# Rover-3_Power_Supply.net
KiCad netlist of a schematic drawn in EAGLE
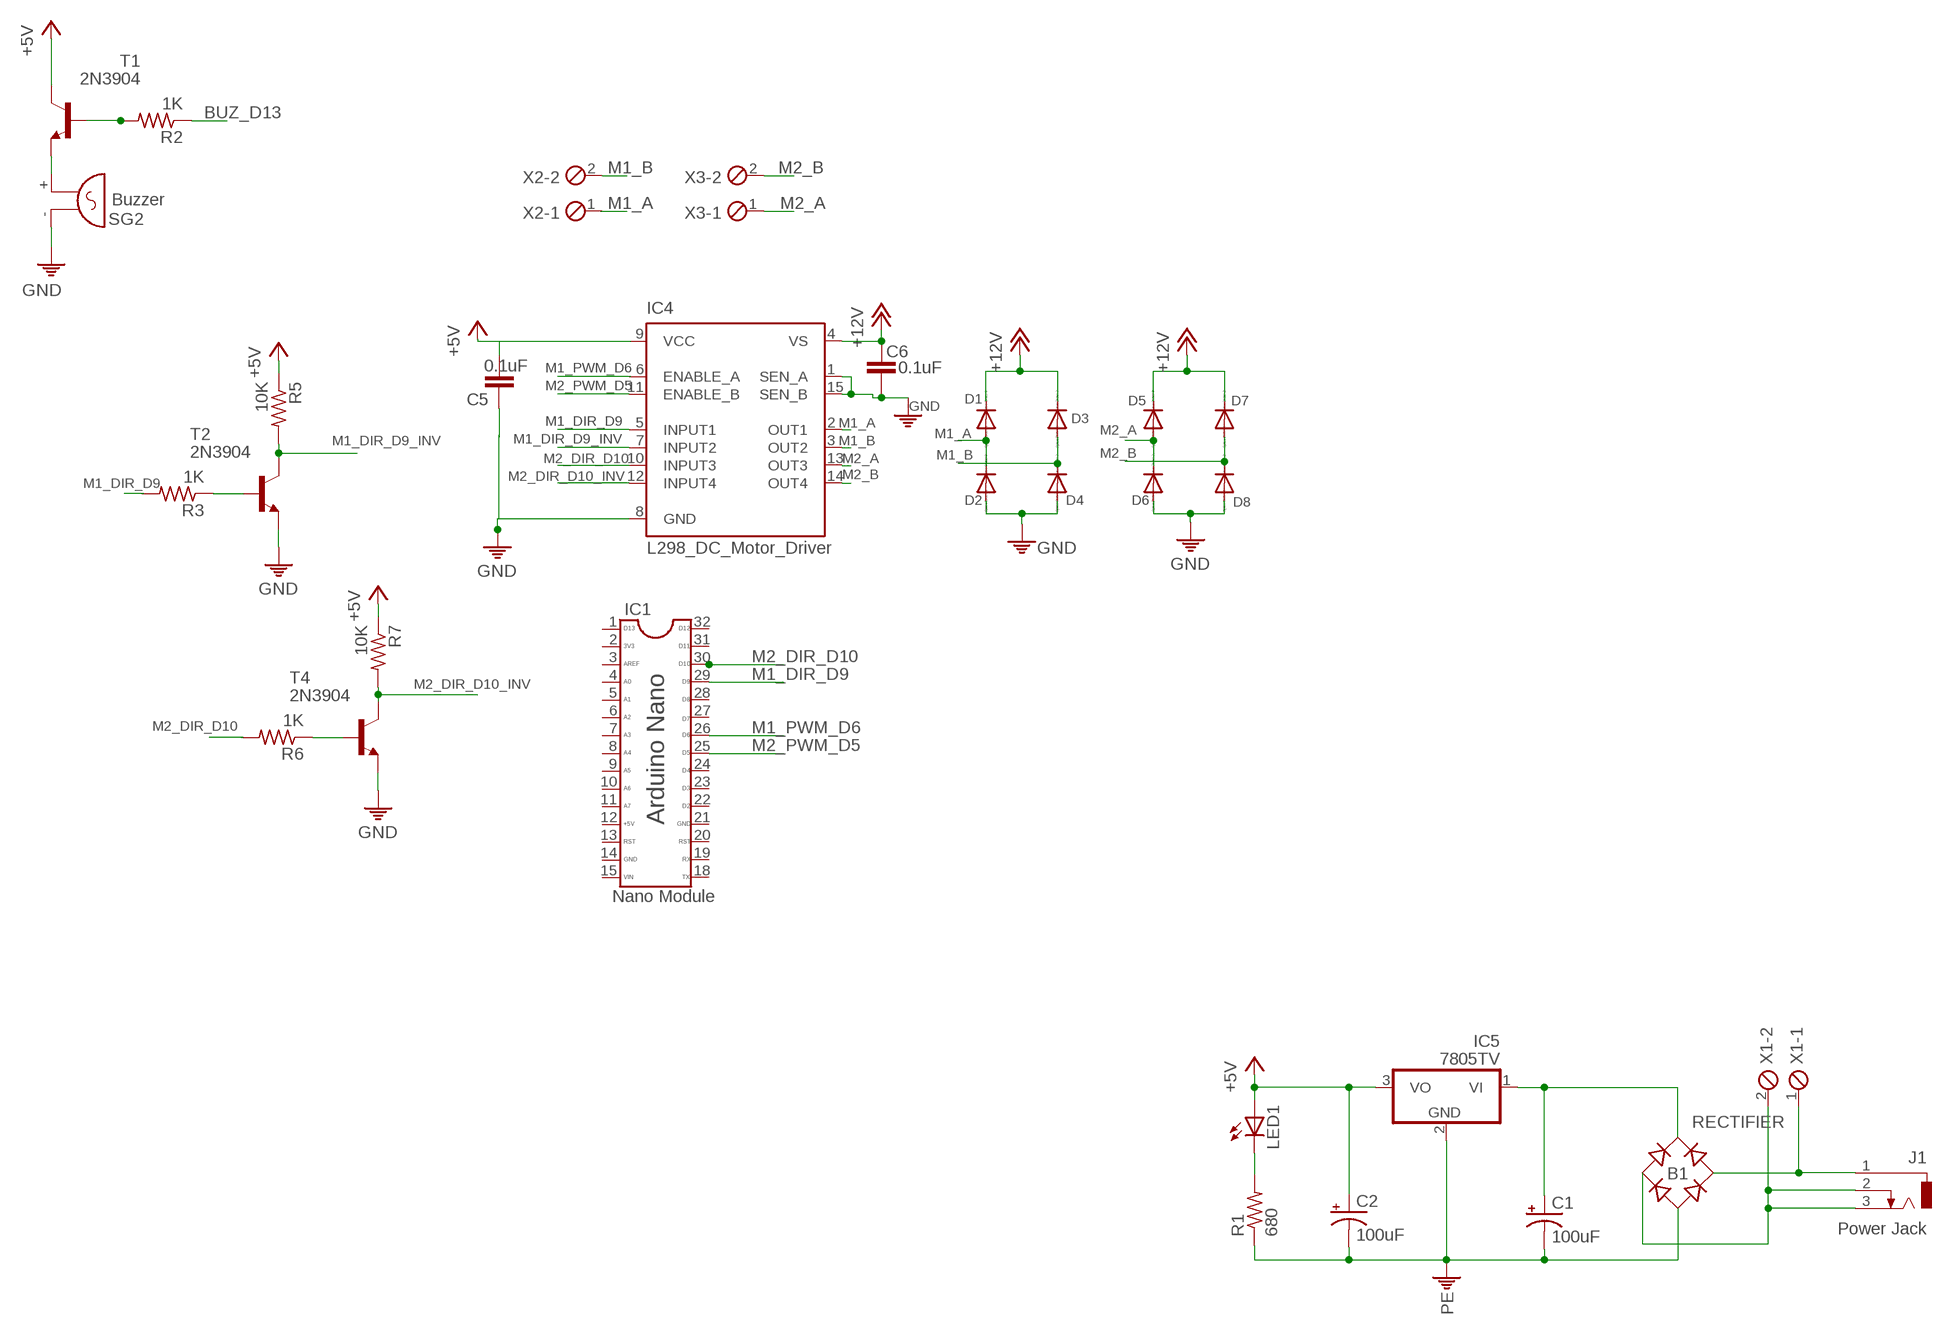
[diagram p0: schematic, sheet 1]

(export (version "E")
  (design (tool "Eeschema 10.0.6"))
  (components
    (comp (ref "B1")
      (value "RECTIFIER")
      (footprint "eagle-import:RB1A")
      (libsource (lib "eagle-import") (part "RB1A"))
    )
    (comp (ref "C1")
      (value "100uF")
      (footprint "eagle-import:E5-8,5")
      (libsource (lib "eagle-import") (part "CPOL-USE5-8.5"))
    )
    (comp (ref "C2")
      (value "100uF")
      (footprint "eagle-import:E5-8,5")
      (libsource (lib "eagle-import") (part "CPOL-USE5-8.5"))
    )
    (comp (ref "C5")
      (value "0.1uF")
      (footprint "eagle-import:C025-024X044")
      (libsource (lib "eagle-import") (part "C-EU025-024X044"))
    )
    (comp (ref "C6")
      (value "0.1uF")
      (footprint "eagle-import:C025-024X044")
      (libsource (lib "eagle-import") (part "C-EU025-024X044"))
    )
    (comp (ref "D1")
      (value "DIODE-D-2.5")
      (footprint "eagle-import:D-2.5")
      (libsource (lib "eagle-import") (part "DIODE-D-2.5"))
    )
    (comp (ref "D2")
      (value "DIODE-D-2.5")
      (footprint "eagle-import:D-2.5")
      (libsource (lib "eagle-import") (part "DIODE-D-2.5"))
    )
    (comp (ref "D3")
      (value "DIODE-D-2.5")
      (footprint "eagle-import:D-2.5")
      (libsource (lib "eagle-import") (part "DIODE-D-2.5"))
    )
    (comp (ref "D4")
      (value "DIODE-D-2.5")
      (footprint "eagle-import:D-2.5")
      (libsource (lib "eagle-import") (part "DIODE-D-2.5"))
    )
    (comp (ref "D5")
      (value "DIODE-D-2.5")
      (footprint "eagle-import:D-2.5")
      (libsource (lib "eagle-import") (part "DIODE-D-2.5"))
    )
    (comp (ref "D6")
      (value "DIODE-D-2.5")
      (footprint "eagle-import:D-2.5")
      (libsource (lib "eagle-import") (part "DIODE-D-2.5"))
    )
    (comp (ref "D7")
      (value "DIODE-D-2.5")
      (footprint "eagle-import:D-2.5")
      (libsource (lib "eagle-import") (part "DIODE-D-2.5"))
    )
    (comp (ref "D8")
      (value "DIODE-D-2.5")
      (footprint "eagle-import:D-2.5")
      (libsource (lib "eagle-import") (part "DIODE-D-2.5"))
    )
    (comp (ref "IC1")
      (value "Nano Module")
      (footprint "eagle-import:DIL32")
      (libsource (lib "eagle-import") (part "DIL32"))
    )
    (comp (ref "IC4")
      (value "L298_DC_Motor_Driver")
      (footprint "eagle-import:MULTIWATT-15")
      (fields (field (name "MPN") "L298N"))
      (libsource (lib "eagle-import") (part "L298"))
    )
    (comp (ref "IC5")
      (value "7805TV")
      (footprint "eagle-import:TO220V")
      (libsource (lib "eagle-import") (part "78TV05"))
    )
    (comp (ref "J1")
      (value "Power Jack")
      (footprint "eagle-import:ROVER-PW-JACL")
      (libsource (lib "eagle-import") (part "DCJ0303"))
    )
    (comp (ref "LED1")
      (value "LED3MM")
      (footprint "eagle-import:LED3MM")
      (libsource (lib "eagle-import") (part "LED3MM"))
    )
    (comp (ref "R1")
      (value "680")
      (footprint "eagle-import:0204_5")
      (libsource (lib "eagle-import") (part "R-US_0204/5"))
    )
    (comp (ref "R2")
      (value "1K")
      (footprint "eagle-import:0204_5")
      (libsource (lib "eagle-import") (part "R-US_0204/5"))
    )
    (comp (ref "R3")
      (value "1K")
      (footprint "eagle-import:0204_5")
      (libsource (lib "eagle-import") (part "R-US_0204/5"))
    )
    (comp (ref "R5")
      (value "10K")
      (footprint "eagle-import:0204_5")
      (libsource (lib "eagle-import") (part "R-US_0204/5"))
    )
    (comp (ref "R6")
      (value "1K")
      (footprint "eagle-import:0204_5")
      (libsource (lib "eagle-import") (part "R-US_0204/5"))
    )
    (comp (ref "R7")
      (value "10K")
      (footprint "eagle-import:0204_5")
      (libsource (lib "eagle-import") (part "R-US_0204/5"))
    )
    (comp (ref "SG2")
      (value "Buzzer")
      (footprint "eagle-import:F_QMX")
      (libsource (lib "eagle-import") (part "F/QMX"))
    )
    (comp (ref "T1")
      (value "2N3904")
      (footprint "eagle-import:TO92")
      (libsource (lib "eagle-import") (part "2N3904"))
    )
    (comp (ref "T2")
      (value "2N3904")
      (footprint "eagle-import:TO92")
      (libsource (lib "eagle-import") (part "2N3904"))
    )
    (comp (ref "T4")
      (value "2N3904")
      (footprint "eagle-import:TO92")
      (libsource (lib "eagle-import") (part "2N3904"))
    )
    (comp (ref "X1")
      (value "MPT2")
      (footprint "eagle-import:2POL254")
      (libsource (lib "eagle-import") (part "MPT2"))
    )
    (comp (ref "X2")
      (value "MPT2")
      (footprint "eagle-import:2POL254")
      (libsource (lib "eagle-import") (part "MPT2"))
    )
    (comp (ref "X3")
      (value "MPT2")
      (footprint "eagle-import:2POL254")
      (libsource (lib "eagle-import") (part "MPT2"))
    )
  )
  (nets
    (net (code "1") (name "+5V") (class "Default")
      (node (ref "C2") (pin "+") (pinfunction "+_+") (pintype "passive"))
      (node (ref "C5") (pin "2") (pinfunction "2_2") (pintype "passive"))
      (node (ref "IC5") (pin "3") (pinfunction "VO_3") (pintype "passive"))
      (node (ref "LED1") (pin "A") (pinfunction "A_A") (pintype "passive"))
      (node (ref "R5") (pin "1") (pinfunction "1_1") (pintype "passive"))
      (node (ref "R7") (pin "1") (pinfunction "1_1") (pintype "passive"))
      (node (ref "T1") (pin "1") (pinfunction "C_1") (pintype "passive"))
    )
    (net (code "2") (name "+12V") (class "Default")
      (node (ref "C6") (pin "2") (pinfunction "2_2") (pintype "passive"))
      (node (ref "D1") (pin "C") (pinfunction "C_C") (pintype "passive"))
      (node (ref "D3") (pin "C") (pinfunction "C_C") (pintype "passive"))
      (node (ref "D5") (pin "C") (pinfunction "C_C") (pintype "passive"))
      (node (ref "D7") (pin "C") (pinfunction "C_C") (pintype "passive"))
      (node (ref "IC4") (pin "4") (pinfunction "VS_4") (pintype "power_in"))
    )
    (net (code "3") (name "/BUZ_D13") (class "Default")
      (node (ref "R2") (pin "1") (pinfunction "1_1") (pintype "passive"))
    )
    (net (code "4") (name "/M1_A") (class "Default")
      (node (ref "D1") (pin "A") (pinfunction "A_A") (pintype "passive"))
      (node (ref "D2") (pin "C") (pinfunction "C_C") (pintype "passive"))
      (node (ref "IC4") (pin "2") (pinfunction "OUT1_2") (pintype "output"))
    )
    (net (code "5") (name "/M1_B") (class "Default")
      (node (ref "D3") (pin "A") (pinfunction "A_A") (pintype "passive"))
      (node (ref "D4") (pin "C") (pinfunction "C_C") (pintype "passive"))
      (node (ref "IC4") (pin "3") (pinfunction "OUT2_3") (pintype "output"))
      (node (ref "X2") (pin "2") (pinfunction "1_2") (pintype "passive"))
    )
    (net (code "6") (name "/M1_DIR_D9") (class "Default")
      (node (ref "IC1") (pin "29") (pinfunction "D9/PWM_29") (pintype "passive"))
      (node (ref "IC4") (pin "5") (pinfunction "INPUT1_5") (pintype "input"))
    )
    (net (code "7") (name "/M1_DIR_D9_INV") (class "Default")
      (node (ref "IC4") (pin "7") (pinfunction "INPUT2_7") (pintype "input"))
      (node (ref "R5") (pin "2") (pinfunction "2_2") (pintype "passive"))
      (node (ref "T2") (pin "1") (pinfunction "C_1") (pintype "passive"))
    )
    (net (code "8") (name "/M1_PWM_D6") (class "Default")
      (node (ref "IC1") (pin "26") (pinfunction "D6/PWM_26") (pintype "passive"))
    )
    (net (code "9") (name "/M2_A") (class "Default")
      (node (ref "D5") (pin "A") (pinfunction "A_A") (pintype "passive"))
      (node (ref "D6") (pin "C") (pinfunction "C_C") (pintype "passive"))
      (node (ref "IC4") (pin "13") (pinfunction "OUT3_13") (pintype "output"))
      (node (ref "X3") (pin "1") (pinfunction "1_1") (pintype "passive"))
    )
    (net (code "10") (name "/M2_B") (class "Default")
      (node (ref "D7") (pin "A") (pinfunction "A_A") (pintype "passive"))
      (node (ref "D8") (pin "C") (pinfunction "C_C") (pintype "passive"))
      (node (ref "IC4") (pin "14") (pinfunction "OUT4_14") (pintype "output"))
      (node (ref "X3") (pin "2") (pinfunction "1_2") (pintype "passive"))
    )
    (net (code "11") (name "/M2_DIR_D10") (class "Default")
      (node (ref "IC1") (pin "30") (pinfunction "D10/PWM_30") (pintype "passive"))
      (node (ref "IC4") (pin "10") (pinfunction "INPUT3_10") (pintype "input"))
    )
    (net (code "12") (name "/M2_DIR_D10_INV") (class "Default")
      (node (ref "IC4") (pin "12") (pinfunction "INPUT4_12") (pintype "input"))
      (node (ref "R7") (pin "2") (pinfunction "2_2") (pintype "passive"))
      (node (ref "T4") (pin "1") (pinfunction "C_1") (pintype "passive"))
    )
    (net (code "13") (name "/M2_PWM_D5") (class "Default")
      (node (ref "IC1") (pin "25") (pinfunction "D5/PWM_25") (pintype "passive"))
      (node (ref "IC4") (pin "11") (pinfunction "ENABLE_B_11") (pintype "input"))
    )
    (net (code "14") (name "/VCC") (class "Default")
      (node (ref "IC4") (pin "9") (pinfunction "VCC_9") (pintype "power_in"))
    )
    (net (code "15") (name "GND") (class "Default")
      (node (ref "B1") (pin "-") (pinfunction "-_-") (pintype "passive"))
      (node (ref "C1") (pin "-") (pinfunction "-_-") (pintype "passive"))
      (node (ref "C2") (pin "-") (pinfunction "-_-") (pintype "passive"))
      (node (ref "C6") (pin "1") (pinfunction "1_1") (pintype "passive"))
      (node (ref "D2") (pin "A") (pinfunction "A_A") (pintype "passive"))
      (node (ref "D4") (pin "A") (pinfunction "A_A") (pintype "passive"))
      (node (ref "D6") (pin "A") (pinfunction "A_A") (pintype "passive"))
      (node (ref "D8") (pin "A") (pinfunction "A_A") (pintype "passive"))
      (node (ref "IC4") (pin "1") (pinfunction "SEN_A_1") (pintype "input"))
      (node (ref "IC4") (pin "15") (pinfunction "SEN_B_15") (pintype "input"))
      (node (ref "IC4") (pin "8") (pinfunction "GND_8") (pintype "power_in"))
      (node (ref "IC5") (pin "2") (pinfunction "GND_2") (pintype "passive"))
      (node (ref "R1") (pin "1") (pinfunction "1_1") (pintype "passive"))
      (node (ref "SG2") (pin "-") (pinfunction "1_-") (pintype "passive"))
      (node (ref "T2") (pin "3") (pinfunction "E_3") (pintype "passive"))
      (node (ref "T4") (pin "3") (pinfunction "E_3") (pintype "passive"))
    )
    (net (code "16") (name "Net-(B1-PadAC1)") (class "Default")
      (node (ref "B1") (pin "AC1") (pinfunction "AC1_AC1") (pintype "passive"))
      (node (ref "J1") (pin "1") (pinfunction "1_1") (pintype "passive"))
      (node (ref "X1") (pin "1") (pinfunction "1_1") (pintype "passive"))
    )
    (net (code "17") (name "Net-(IC5-VI)") (class "Default")
      (node (ref "B1") (pin "+") (pinfunction "+_+") (pintype "passive"))
      (node (ref "C1") (pin "+") (pinfunction "+_+") (pintype "passive"))
      (node (ref "IC5") (pin "1") (pinfunction "VI_1") (pintype "input"))
    )
    (net (code "18") (name "Net-(LED1-C)") (class "Default")
      (node (ref "LED1") (pin "K") (pinfunction "C_K") (pintype "passive"))
      (node (ref "R1") (pin "2") (pinfunction "2_2") (pintype "passive"))
    )
    (net (code "19") (name "Net-(SG2-2)") (class "Default")
      (node (ref "SG2") (pin "+") (pinfunction "2_+") (pintype "passive"))
      (node (ref "T1") (pin "3") (pinfunction "E_3") (pintype "passive"))
    )
    (net (code "20") (name "Net-(T1-B)") (class "Default")
      (node (ref "R2") (pin "2") (pinfunction "2_2") (pintype "passive"))
      (node (ref "T1") (pin "2") (pinfunction "B_2") (pintype "passive"))
    )
    (net (code "21") (name "Net-(T2-B)") (class "Default")
      (node (ref "R3") (pin "1") (pinfunction "1_1") (pintype "passive"))
      (node (ref "T2") (pin "2") (pinfunction "B_2") (pintype "passive"))
    )
    (net (code "22") (name "Net-(T4-B)") (class "Default")
      (node (ref "R6") (pin "1") (pinfunction "1_1") (pintype "passive"))
      (node (ref "T4") (pin "2") (pinfunction "B_2") (pintype "passive"))
    )
    (net (code "23") (name "Net-(X1B-1)") (class "Default")
      (node (ref "B1") (pin "AC2") (pinfunction "AC2_AC2") (pintype "passive"))
      (node (ref "J1") (pin "2") (pinfunction "2_2") (pintype "passive"))
      (node (ref "J1") (pin "3") (pinfunction "3_3") (pintype "passive"))
      (node (ref "X1") (pin "2") (pinfunction "1_2") (pintype "passive"))
    )
    (net (code "24") (name "unconnected-(C5-Pad1)") (class "Default")
      (node (ref "C5") (pin "1") (pinfunction "1_1") (pintype "passive"))
    )
    (net (code "25") (name "unconnected-(IC1-3V3-Pad2)") (class "Default")
      (node (ref "IC1") (pin "2") (pinfunction "3V3_2") (pintype "passive"))
    )
    (net (code "26") (name "unconnected-(IC1-5V-Pad12)") (class "Default")
      (node (ref "IC1") (pin "12") (pinfunction "5V_12") (pintype "passive"))
    )
    (net (code "27") (name "unconnected-(IC1-A0{slash}D14-Pad4)") (class "Default")
      (node (ref "IC1") (pin "4") (pinfunction "A0/D14_4") (pintype "passive"))
    )
    (net (code "28") (name "unconnected-(IC1-A1{slash}D15-Pad5)") (class "Default")
      (node (ref "IC1") (pin "5") (pinfunction "A1/D15_5") (pintype "passive"))
    )
    (net (code "29") (name "unconnected-(IC1-A2{slash}D16-Pad6)") (class "Default")
      (node (ref "IC1") (pin "6") (pinfunction "A2/D16_6") (pintype "passive"))
    )
    (net (code "30") (name "unconnected-(IC1-A3{slash}D17-Pad7)") (class "Default")
      (node (ref "IC1") (pin "7") (pinfunction "A3/D17_7") (pintype "passive"))
    )
    (net (code "31") (name "unconnected-(IC1-A4{slash}D18{slash}SDA-Pad8)") (class "Default")
      (node (ref "IC1") (pin "8") (pinfunction "A4/D18/SDA_8") (pintype "passive"))
    )
    (net (code "32") (name "unconnected-(IC1-A5{slash}D19{slash}SCL-Pad9)") (class "Default")
      (node (ref "IC1") (pin "9") (pinfunction "A5/D19/SCL_9") (pintype "passive"))
    )
    (net (code "33") (name "unconnected-(IC1-A6-Pad10)") (class "Default")
      (node (ref "IC1") (pin "10") (pinfunction "A6_10") (pintype "passive"))
    )
    (net (code "34") (name "unconnected-(IC1-A7-Pad11)") (class "Default")
      (node (ref "IC1") (pin "11") (pinfunction "A7_11") (pintype "passive"))
    )
    (net (code "35") (name "unconnected-(IC1-AREF-Pad3)") (class "Default")
      (node (ref "IC1") (pin "3") (pinfunction "AREF_3") (pintype "passive"))
    )
    (net (code "36") (name "unconnected-(IC1-D2-Pad22)") (class "Default")
      (node (ref "IC1") (pin "22") (pinfunction "D2_22") (pintype "passive"))
    )
    (net (code "37") (name "unconnected-(IC1-D3-Pad23)") (class "Default")
      (node (ref "IC1") (pin "23") (pinfunction "D3_23") (pintype "passive"))
    )
    (net (code "38") (name "unconnected-(IC1-D4-Pad24)") (class "Default")
      (node (ref "IC1") (pin "24") (pinfunction "D4_24") (pintype "passive"))
    )
    (net (code "39") (name "unconnected-(IC1-D7-Pad27)") (class "Default")
      (node (ref "IC1") (pin "27") (pinfunction "D7_27") (pintype "passive"))
    )
    (net (code "40") (name "unconnected-(IC1-D8-Pad28)") (class "Default")
      (node (ref "IC1") (pin "28") (pinfunction "D8_28") (pintype "passive"))
    )
    (net (code "41") (name "unconnected-(IC1-D11{slash}MOSI-Pad31)") (class "Default")
      (node (ref "IC1") (pin "31") (pinfunction "D11/MOSI_31") (pintype "passive"))
    )
    (net (code "42") (name "unconnected-(IC1-D12{slash}MISO-Pad32)") (class "Default")
      (node (ref "IC1") (pin "32") (pinfunction "D12/MISO_32") (pintype "passive"))
    )
    (net (code "43") (name "unconnected-(IC1-D13-Pad1)") (class "Default")
      (node (ref "IC1") (pin "1") (pinfunction "D13_1") (pintype "passive"))
    )
    (net (code "44") (name "unconnected-(IC1-GND1-Pad14)") (class "Default")
      (node (ref "IC1") (pin "14") (pinfunction "GND1_14") (pintype "passive"))
    )
    (net (code "45") (name "unconnected-(IC1-GND2-Pad21)") (class "Default")
      (node (ref "IC1") (pin "21") (pinfunction "GND2_21") (pintype "passive"))
    )
    (net (code "46") (name "unconnected-(IC1-RST1-Pad13)") (class "Default")
      (node (ref "IC1") (pin "13") (pinfunction "RST1_13") (pintype "passive"))
    )
    (net (code "47") (name "unconnected-(IC1-RST2-Pad20)") (class "Default")
      (node (ref "IC1") (pin "20") (pinfunction "RST2_20") (pintype "passive"))
    )
    (net (code "48") (name "unconnected-(IC1-RX-Pad19)") (class "Default")
      (node (ref "IC1") (pin "19") (pinfunction "RX_19") (pintype "passive"))
    )
    (net (code "49") (name "unconnected-(IC1-TX-Pad18)") (class "Default")
      (node (ref "IC1") (pin "18") (pinfunction "TX_18") (pintype "passive"))
    )
    (net (code "50") (name "unconnected-(IC1-VIN-Pad15)") (class "Default")
      (node (ref "IC1") (pin "15") (pinfunction "VIN_15") (pintype "passive"))
    )
    (net (code "51") (name "unconnected-(IC4-ENABLE_A-Pad6)") (class "Default")
      (node (ref "IC4") (pin "6") (pinfunction "ENABLE_A_6") (pintype "input"))
    )
    (net (code "52") (name "unconnected-(R3-Pad2)") (class "Default")
      (node (ref "R3") (pin "2") (pinfunction "2_2") (pintype "passive"))
    )
    (net (code "53") (name "unconnected-(R6-Pad2)") (class "Default")
      (node (ref "R6") (pin "2") (pinfunction "2_2") (pintype "passive"))
    )
    (net (code "54") (name "unconnected-(X2-Pad1)") (class "Default")
      (node (ref "X2") (pin "1") (pinfunction "1_1") (pintype "passive"))
    )
  )
)
